# IDC_EXT_Connectors.net
KiCad netlist of a schematic drawn in Altium Designer
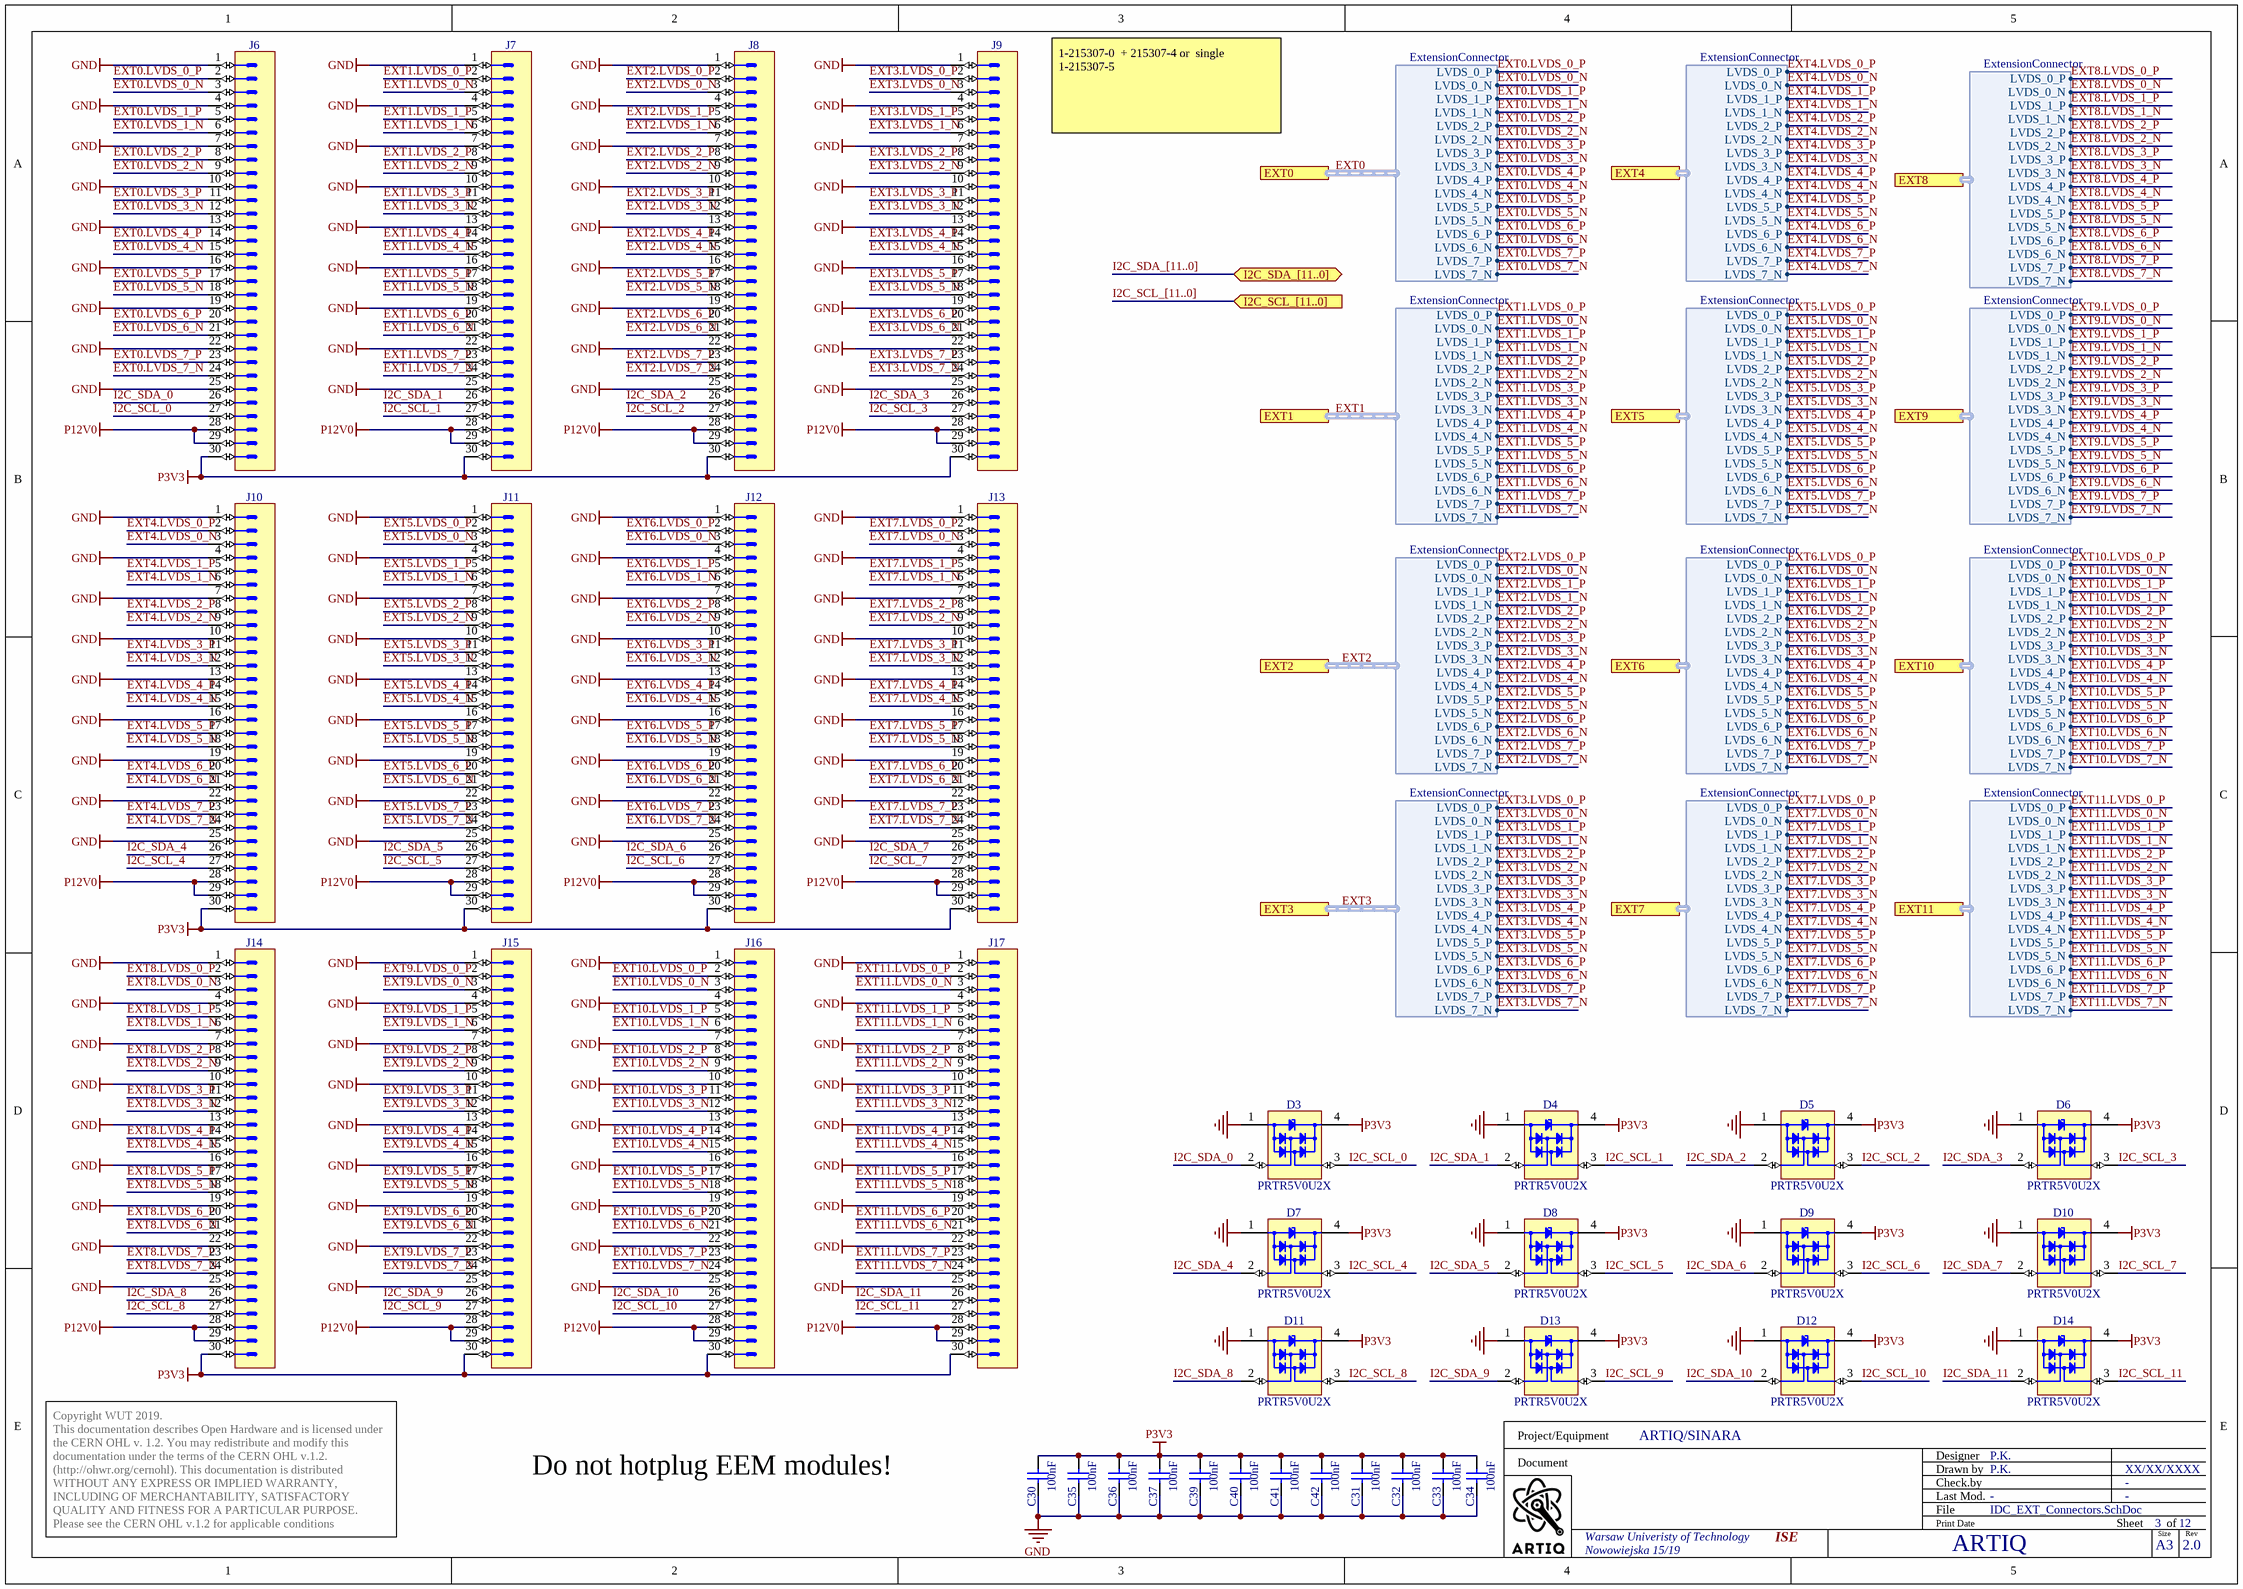
[diagram p0: IDC_EXT_Connectors.SchDoc]

(export (version "E")
  (design (tool "Eeschema 10.0.6"))
  (components
    (comp (ref "C30")
      (value "100nF")
      (footprint "CAPC0603X33N")
      (description "Non-polarised capacitor")
      (fields
        (field (name "PART NUMBER") "CC0201_100NF_6.3V_10%_X5R")
        (field (name "VOLTAGE") "6.3V")
        (field (name "AUTHOR") "CERN DEM JLC")
      )
      (libsource (lib "Capacitors") (part "Capacitor - non polarized"))
    )
    (comp (ref "C31")
      (value "100nF")
      (footprint "CAPC0603X33N")
      (description "Non-polarised capacitor")
      (fields
        (field (name "PART NUMBER") "CC0201_100NF_6.3V_10%_X5R")
        (field (name "VOLTAGE") "6.3V")
        (field (name "AUTHOR") "CERN DEM JLC")
      )
      (libsource (lib "Capacitors") (part "Capacitor - non polarized"))
    )
    (comp (ref "C32")
      (value "100nF")
      (footprint "CAPC0603X33N")
      (description "Non-polarised capacitor")
      (fields
        (field (name "PART NUMBER") "CC0201_100NF_6.3V_10%_X5R")
        (field (name "VOLTAGE") "6.3V")
        (field (name "AUTHOR") "CERN DEM JLC")
      )
      (libsource (lib "Capacitors") (part "Capacitor - non polarized"))
    )
    (comp (ref "C33")
      (value "100nF")
      (footprint "CAPC0603X33N")
      (description "Non-polarised capacitor")
      (fields
        (field (name "PART NUMBER") "CC0201_100NF_6.3V_10%_X5R")
        (field (name "VOLTAGE") "6.3V")
        (field (name "AUTHOR") "CERN DEM JLC")
      )
      (libsource (lib "Capacitors") (part "Capacitor - non polarized"))
    )
    (comp (ref "C34")
      (value "100nF")
      (footprint "CAPC0603X33N")
      (description "Non-polarised capacitor")
      (fields
        (field (name "PART NUMBER") "CC0201_100NF_6.3V_10%_X5R")
        (field (name "VOLTAGE") "6.3V")
        (field (name "AUTHOR") "CERN DEM JLC")
      )
      (libsource (lib "Capacitors") (part "Capacitor - non polarized"))
    )
    (comp (ref "C35")
      (value "100nF")
      (footprint "CAPC0603X33N")
      (description "Non-polarised capacitor")
      (fields
        (field (name "PART NUMBER") "CC0201_100NF_6.3V_10%_X5R")
        (field (name "VOLTAGE") "6.3V")
        (field (name "AUTHOR") "CERN DEM JLC")
      )
      (libsource (lib "Capacitors") (part "Capacitor - non polarized"))
    )
    (comp (ref "C36")
      (value "100nF")
      (footprint "CAPC0603X33N")
      (description "Non-polarised capacitor")
      (fields
        (field (name "PART NUMBER") "CC0201_100NF_6.3V_10%_X5R")
        (field (name "VOLTAGE") "6.3V")
        (field (name "AUTHOR") "CERN DEM JLC")
      )
      (libsource (lib "Capacitors") (part "Capacitor - non polarized"))
    )
    (comp (ref "C37")
      (value "100nF")
      (footprint "CAPC0603X33N")
      (description "Non-polarised capacitor")
      (fields
        (field (name "PART NUMBER") "CC0201_100NF_6.3V_10%_X5R")
        (field (name "VOLTAGE") "6.3V")
        (field (name "AUTHOR") "CERN DEM JLC")
      )
      (libsource (lib "Capacitors") (part "Capacitor - non polarized"))
    )
    (comp (ref "C39")
      (value "100nF")
      (footprint "CAPC0603X33N")
      (description "Non-polarised capacitor")
      (fields
        (field (name "PART NUMBER") "CC0201_100NF_6.3V_10%_X5R")
        (field (name "VOLTAGE") "6.3V")
        (field (name "AUTHOR") "CERN DEM JLC")
      )
      (libsource (lib "Capacitors") (part "Capacitor - non polarized"))
    )
    (comp (ref "C40")
      (value "100nF")
      (footprint "CAPC0603X33N")
      (description "Non-polarised capacitor")
      (fields
        (field (name "PART NUMBER") "CC0201_100NF_6.3V_10%_X5R")
        (field (name "VOLTAGE") "6.3V")
        (field (name "AUTHOR") "CERN DEM JLC")
      )
      (libsource (lib "Capacitors") (part "Capacitor - non polarized"))
    )
    (comp (ref "C41")
      (value "100nF")
      (footprint "CAPC0603X33N")
      (description "Non-polarised capacitor")
      (fields
        (field (name "PART NUMBER") "CC0201_100NF_6.3V_10%_X5R")
        (field (name "VOLTAGE") "6.3V")
        (field (name "AUTHOR") "CERN DEM JLC")
      )
      (libsource (lib "Capacitors") (part "Capacitor - non polarized"))
    )
    (comp (ref "C42")
      (value "100nF")
      (footprint "CAPC0603X33N")
      (description "Non-polarised capacitor")
      (fields
        (field (name "PART NUMBER") "CC0201_100NF_6.3V_10%_X5R")
        (field (name "VOLTAGE") "6.3V")
        (field (name "AUTHOR") "CERN DEM JLC")
      )
      (libsource (lib "Capacitors") (part "Capacitor - non polarized"))
    )
    (comp (ref "D3")
      (value "PRTR5V0U2X")
      (footprint "SOT190P230X110-4N")
      (description "Ultra Low Capacitance Double Rail-to-Rail ESD Protection Diode")
      (fields
        (field (name "VOLTAGE") "5.5V")
        (field (name "MANUFACTURER") "NXP SEMICONDUCTORS")
        (field (name "AUTHOR") "CERN DEM JLC")
      )
      (libsource (lib "ICs And Semiconductors") (part "PRTR5V0U2X"))
    )
    (comp (ref "D4")
      (value "PRTR5V0U2X")
      (footprint "SOT190P230X110-4N")
      (description "Ultra Low Capacitance Double Rail-to-Rail ESD Protection Diode")
      (fields
        (field (name "VOLTAGE") "5.5V")
        (field (name "MANUFACTURER") "NXP SEMICONDUCTORS")
        (field (name "AUTHOR") "CERN DEM JLC")
      )
      (libsource (lib "ICs And Semiconductors") (part "PRTR5V0U2X"))
    )
    (comp (ref "D5")
      (value "PRTR5V0U2X")
      (footprint "SOT190P230X110-4N")
      (description "Ultra Low Capacitance Double Rail-to-Rail ESD Protection Diode")
      (fields
        (field (name "VOLTAGE") "5.5V")
        (field (name "MANUFACTURER") "NXP SEMICONDUCTORS")
        (field (name "AUTHOR") "CERN DEM JLC")
      )
      (libsource (lib "ICs And Semiconductors") (part "PRTR5V0U2X"))
    )
    (comp (ref "D6")
      (value "PRTR5V0U2X")
      (footprint "SOT190P230X110-4N")
      (description "Ultra Low Capacitance Double Rail-to-Rail ESD Protection Diode")
      (fields
        (field (name "VOLTAGE") "5.5V")
        (field (name "MANUFACTURER") "NXP SEMICONDUCTORS")
        (field (name "AUTHOR") "CERN DEM JLC")
      )
      (libsource (lib "ICs And Semiconductors") (part "PRTR5V0U2X"))
    )
    (comp (ref "D7")
      (value "PRTR5V0U2X")
      (footprint "SOT190P230X110-4N")
      (description "Ultra Low Capacitance Double Rail-to-Rail ESD Protection Diode")
      (fields
        (field (name "VOLTAGE") "5.5V")
        (field (name "MANUFACTURER") "NXP SEMICONDUCTORS")
        (field (name "AUTHOR") "CERN DEM JLC")
      )
      (libsource (lib "ICs And Semiconductors") (part "PRTR5V0U2X"))
    )
    (comp (ref "D8")
      (value "PRTR5V0U2X")
      (footprint "SOT190P230X110-4N")
      (description "Ultra Low Capacitance Double Rail-to-Rail ESD Protection Diode")
      (fields
        (field (name "VOLTAGE") "5.5V")
        (field (name "MANUFACTURER") "NXP SEMICONDUCTORS")
        (field (name "AUTHOR") "CERN DEM JLC")
      )
      (libsource (lib "ICs And Semiconductors") (part "PRTR5V0U2X"))
    )
    (comp (ref "D9")
      (value "PRTR5V0U2X")
      (footprint "SOT190P230X110-4N")
      (description "Ultra Low Capacitance Double Rail-to-Rail ESD Protection Diode")
      (fields
        (field (name "VOLTAGE") "5.5V")
        (field (name "MANUFACTURER") "NXP SEMICONDUCTORS")
        (field (name "AUTHOR") "CERN DEM JLC")
      )
      (libsource (lib "ICs And Semiconductors") (part "PRTR5V0U2X"))
    )
    (comp (ref "D10")
      (value "PRTR5V0U2X")
      (footprint "SOT190P230X110-4N")
      (description "Ultra Low Capacitance Double Rail-to-Rail ESD Protection Diode")
      (fields
        (field (name "VOLTAGE") "5.5V")
        (field (name "MANUFACTURER") "NXP SEMICONDUCTORS")
        (field (name "AUTHOR") "CERN DEM JLC")
      )
      (libsource (lib "ICs And Semiconductors") (part "PRTR5V0U2X"))
    )
    (comp (ref "D11")
      (value "PRTR5V0U2X")
      (footprint "SOT190P230X110-4N")
      (description "Ultra Low Capacitance Double Rail-to-Rail ESD Protection Diode")
      (fields
        (field (name "VOLTAGE") "5.5V")
        (field (name "MANUFACTURER") "NXP SEMICONDUCTORS")
        (field (name "AUTHOR") "CERN DEM JLC")
      )
      (libsource (lib "ICs And Semiconductors") (part "PRTR5V0U2X"))
    )
    (comp (ref "D12")
      (value "PRTR5V0U2X")
      (footprint "SOT190P230X110-4N")
      (description "Ultra Low Capacitance Double Rail-to-Rail ESD Protection Diode")
      (fields
        (field (name "VOLTAGE") "5.5V")
        (field (name "MANUFACTURER") "NXP SEMICONDUCTORS")
        (field (name "AUTHOR") "CERN DEM JLC")
      )
      (libsource (lib "ICs And Semiconductors") (part "PRTR5V0U2X"))
    )
    (comp (ref "D13")
      (value "PRTR5V0U2X")
      (footprint "SOT190P230X110-4N")
      (description "Ultra Low Capacitance Double Rail-to-Rail ESD Protection Diode")
      (fields
        (field (name "VOLTAGE") "5.5V")
        (field (name "MANUFACTURER") "NXP SEMICONDUCTORS")
        (field (name "AUTHOR") "CERN DEM JLC")
      )
      (libsource (lib "ICs And Semiconductors") (part "PRTR5V0U2X"))
    )
    (comp (ref "D14")
      (value "PRTR5V0U2X")
      (footprint "SOT190P230X110-4N")
      (description "Ultra Low Capacitance Double Rail-to-Rail ESD Protection Diode")
      (fields
        (field (name "VOLTAGE") "5.5V")
        (field (name "MANUFACTURER") "NXP SEMICONDUCTORS")
        (field (name "AUTHOR") "CERN DEM JLC")
      )
      (libsource (lib "ICs And Semiconductors") (part "PRTR5V0U2X"))
    )
    (comp (ref "J6")
      (value "AMPMODU")
      (footprint "TYCO_1-215307-5")
      (description "Connector 2.54mm, 30 pin female, vertical, 7mm, AMPMODU HV-100/HV-190")
      (fields
        (field (name "PART NUMBER") "TYCO_1-215307-5")
        (field (name "MANUFACTURER") "TYCO ELECTRONICS")
        (field (name "AUTHOR") "GK")
      )
      (libsource (lib "LIBRARY_SCH") (part "CON_2x15_2.54_female_V_mirror"))
    )
    (comp (ref "J7")
      (value "AMPMODU")
      (footprint "TYCO_1-215307-5")
      (description "Connector 2.54mm, 30 pin female, vertical, 7mm, AMPMODU HV-100/HV-190")
      (fields
        (field (name "PART NUMBER") "TYCO_1-215307-5")
        (field (name "MANUFACTURER") "TYCO ELECTRONICS")
        (field (name "AUTHOR") "GK")
      )
      (libsource (lib "LIBRARY_SCH") (part "CON_2x15_2.54_female_V_mirror"))
    )
    (comp (ref "J8")
      (value "AMPMODU")
      (footprint "TYCO_1-215307-5")
      (description "Connector 2.54mm, 30 pin female, vertical, 7mm, AMPMODU HV-100/HV-190")
      (fields
        (field (name "PART NUMBER") "TYCO_1-215307-5")
        (field (name "MANUFACTURER") "TYCO ELECTRONICS")
        (field (name "AUTHOR") "GK")
      )
      (libsource (lib "LIBRARY_SCH") (part "CON_2x15_2.54_female_V_mirror"))
    )
    (comp (ref "J9")
      (value "AMPMODU")
      (footprint "TYCO_1-215307-5")
      (description "Connector 2.54mm, 30 pin female, vertical, 7mm, AMPMODU HV-100/HV-190")
      (fields
        (field (name "PART NUMBER") "TYCO_1-215307-5")
        (field (name "MANUFACTURER") "TYCO ELECTRONICS")
        (field (name "AUTHOR") "GK")
      )
      (libsource (lib "LIBRARY_SCH") (part "CON_2x15_2.54_female_V_mirror"))
    )
    (comp (ref "J10")
      (value "AMPMODU")
      (footprint "TYCO_1-215307-5")
      (description "Connector 2.54mm, 30 pin female, vertical, 7mm, AMPMODU HV-100/HV-190")
      (fields
        (field (name "PART NUMBER") "TYCO_1-215307-5")
        (field (name "MANUFACTURER") "TYCO ELECTRONICS")
        (field (name "AUTHOR") "GK")
      )
      (libsource (lib "LIBRARY_SCH") (part "CON_2x15_2.54_female_V_mirror"))
    )
    (comp (ref "J11")
      (value "AMPMODU")
      (footprint "TYCO_1-215307-5")
      (description "Connector 2.54mm, 30 pin female, vertical, 7mm, AMPMODU HV-100/HV-190")
      (fields
        (field (name "PART NUMBER") "TYCO_1-215307-5")
        (field (name "MANUFACTURER") "TYCO ELECTRONICS")
        (field (name "AUTHOR") "GK")
      )
      (libsource (lib "LIBRARY_SCH") (part "CON_2x15_2.54_female_V_mirror"))
    )
    (comp (ref "J12")
      (value "AMPMODU")
      (footprint "TYCO_1-215307-5")
      (description "Connector 2.54mm, 30 pin female, vertical, 7mm, AMPMODU HV-100/HV-190")
      (fields
        (field (name "PART NUMBER") "TYCO_1-215307-5")
        (field (name "MANUFACTURER") "TYCO ELECTRONICS")
        (field (name "AUTHOR") "GK")
      )
      (libsource (lib "LIBRARY_SCH") (part "CON_2x15_2.54_female_V_mirror"))
    )
    (comp (ref "J13")
      (value "AMPMODU")
      (footprint "TYCO_1-215307-5")
      (description "Connector 2.54mm, 30 pin female, vertical, 7mm, AMPMODU HV-100/HV-190")
      (fields
        (field (name "PART NUMBER") "TYCO_1-215307-5")
        (field (name "MANUFACTURER") "TYCO ELECTRONICS")
        (field (name "AUTHOR") "GK")
      )
      (libsource (lib "LIBRARY_SCH") (part "CON_2x15_2.54_female_V_mirror"))
    )
    (comp (ref "J14")
      (value "AMPMODU")
      (footprint "TYCO_1-215307-5")
      (description "Connector 2.54mm, 30 pin female, vertical, 7mm, AMPMODU HV-100/HV-190")
      (fields
        (field (name "PART NUMBER") "TYCO_1-215307-5")
        (field (name "MANUFACTURER") "TYCO ELECTRONICS")
        (field (name "AUTHOR") "GK")
      )
      (libsource (lib "LIBRARY_SCH") (part "CON_2x15_2.54_female_V_mirror"))
    )
    (comp (ref "J15")
      (value "AMPMODU")
      (footprint "TYCO_1-215307-5")
      (description "Connector 2.54mm, 30 pin female, vertical, 7mm, AMPMODU HV-100/HV-190")
      (fields
        (field (name "PART NUMBER") "TYCO_1-215307-5")
        (field (name "MANUFACTURER") "TYCO ELECTRONICS")
        (field (name "AUTHOR") "GK")
      )
      (libsource (lib "LIBRARY_SCH") (part "CON_2x15_2.54_female_V_mirror"))
    )
    (comp (ref "J16")
      (value "AMPMODU")
      (footprint "TYCO_1-215307-5")
      (description "Connector 2.54mm, 30 pin female, vertical, 7mm, AMPMODU HV-100/HV-190")
      (fields
        (field (name "PART NUMBER") "TYCO_1-215307-5")
        (field (name "MANUFACTURER") "TYCO ELECTRONICS")
        (field (name "AUTHOR") "GK")
      )
      (libsource (lib "LIBRARY_SCH") (part "CON_2x15_2.54_female_V_mirror"))
    )
    (comp (ref "J17")
      (value "AMPMODU")
      (footprint "TYCO_1-215307-5")
      (description "Connector 2.54mm, 30 pin female, vertical, 7mm, AMPMODU HV-100/HV-190")
      (fields
        (field (name "PART NUMBER") "TYCO_1-215307-5")
        (field (name "MANUFACTURER") "TYCO ELECTRONICS")
        (field (name "AUTHOR") "GK")
      )
      (libsource (lib "LIBRARY_SCH") (part "CON_2x15_2.54_female_V_mirror"))
    )
  )
  (nets
    (net (code "6") (name "/EXT0.LVDS_0_N") (class "Default")
      (node (ref "J6") (pin "3") (pinfunction "3_3") (pintype "bidirectional"))
    )
    (net (code "7") (name "/EXT0.LVDS_0_P") (class "Default")
      (node (ref "J6") (pin "2") (pinfunction "2_2") (pintype "bidirectional"))
    )
    (net (code "8") (name "/EXT0.LVDS_1_N") (class "Default")
      (node (ref "J6") (pin "6") (pinfunction "6_6") (pintype "bidirectional"))
    )
    (net (code "9") (name "/EXT0.LVDS_1_P") (class "Default")
      (node (ref "J6") (pin "5") (pinfunction "5_5") (pintype "bidirectional"))
    )
    (net (code "10") (name "/EXT0.LVDS_2_N") (class "Default")
      (node (ref "J6") (pin "9") (pinfunction "9_9") (pintype "bidirectional"))
    )
    (net (code "11") (name "/EXT0.LVDS_2_P") (class "Default")
      (node (ref "J6") (pin "8") (pinfunction "8_8") (pintype "bidirectional"))
    )
    (net (code "12") (name "/EXT0.LVDS_3_N") (class "Default")
      (node (ref "J6") (pin "12") (pinfunction "12_12") (pintype "bidirectional"))
    )
    (net (code "13") (name "/EXT0.LVDS_3_P") (class "Default")
      (node (ref "J6") (pin "11") (pinfunction "11_11") (pintype "bidirectional"))
    )
    (net (code "14") (name "/EXT0.LVDS_4_N") (class "Default")
      (node (ref "J6") (pin "15") (pinfunction "15_15") (pintype "bidirectional"))
    )
    (net (code "15") (name "/EXT0.LVDS_4_P") (class "Default")
      (node (ref "J6") (pin "14") (pinfunction "14_14") (pintype "bidirectional"))
    )
    (net (code "16") (name "/EXT0.LVDS_5_N") (class "Default")
      (node (ref "J6") (pin "18") (pinfunction "18_18") (pintype "bidirectional"))
    )
    (net (code "17") (name "/EXT0.LVDS_5_P") (class "Default")
      (node (ref "J6") (pin "17") (pinfunction "17_17") (pintype "bidirectional"))
    )
    (net (code "18") (name "/EXT0.LVDS_6_N") (class "Default")
      (node (ref "J6") (pin "21") (pinfunction "21_21") (pintype "bidirectional"))
    )
    (net (code "19") (name "/EXT0.LVDS_6_P") (class "Default")
      (node (ref "J6") (pin "20") (pinfunction "20_20") (pintype "bidirectional"))
    )
    (net (code "20") (name "/EXT0.LVDS_7_N") (class "Default")
      (node (ref "J6") (pin "24") (pinfunction "24_24") (pintype "bidirectional"))
    )
    (net (code "21") (name "/EXT0.LVDS_7_P") (class "Default")
      (node (ref "J6") (pin "23") (pinfunction "23_23") (pintype "bidirectional"))
    )
    (net (code "23") (name "/EXT1.LVDS_0_N") (class "Default")
      (node (ref "J7") (pin "3") (pinfunction "3_3") (pintype "bidirectional"))
    )
    (net (code "24") (name "/EXT1.LVDS_0_P") (class "Default")
      (node (ref "J7") (pin "2") (pinfunction "2_2") (pintype "bidirectional"))
    )
    (net (code "25") (name "/EXT1.LVDS_1_N") (class "Default")
      (node (ref "J7") (pin "6") (pinfunction "6_6") (pintype "bidirectional"))
    )
    (net (code "26") (name "/EXT1.LVDS_1_P") (class "Default")
      (node (ref "J7") (pin "5") (pinfunction "5_5") (pintype "bidirectional"))
    )
    (net (code "27") (name "/EXT1.LVDS_2_N") (class "Default")
      (node (ref "J7") (pin "9") (pinfunction "9_9") (pintype "bidirectional"))
    )
    (net (code "28") (name "/EXT1.LVDS_2_P") (class "Default")
      (node (ref "J7") (pin "8") (pinfunction "8_8") (pintype "bidirectional"))
    )
    (net (code "29") (name "/EXT1.LVDS_3_N") (class "Default")
      (node (ref "J7") (pin "12") (pinfunction "12_12") (pintype "bidirectional"))
    )
    (net (code "30") (name "/EXT1.LVDS_3_P") (class "Default")
      (node (ref "J7") (pin "11") (pinfunction "11_11") (pintype "bidirectional"))
    )
    (net (code "31") (name "/EXT1.LVDS_4_N") (class "Default")
      (node (ref "J7") (pin "15") (pinfunction "15_15") (pintype "bidirectional"))
    )
    (net (code "32") (name "/EXT1.LVDS_4_P") (class "Default")
      (node (ref "J7") (pin "14") (pinfunction "14_14") (pintype "bidirectional"))
    )
    (net (code "33") (name "/EXT1.LVDS_5_N") (class "Default")
      (node (ref "J7") (pin "18") (pinfunction "18_18") (pintype "bidirectional"))
    )
    (net (code "34") (name "/EXT1.LVDS_5_P") (class "Default")
      (node (ref "J7") (pin "17") (pinfunction "17_17") (pintype "bidirectional"))
    )
    (net (code "35") (name "/EXT1.LVDS_6_N") (class "Default")
      (node (ref "J7") (pin "21") (pinfunction "21_21") (pintype "bidirectional"))
    )
    (net (code "36") (name "/EXT1.LVDS_6_P") (class "Default")
      (node (ref "J7") (pin "20") (pinfunction "20_20") (pintype "bidirectional"))
    )
    (net (code "37") (name "/EXT1.LVDS_7_N") (class "Default")
      (node (ref "J7") (pin "24") (pinfunction "24_24") (pintype "bidirectional"))
    )
    (net (code "38") (name "/EXT1.LVDS_7_P") (class "Default")
      (node (ref "J7") (pin "23") (pinfunction "23_23") (pintype "bidirectional"))
    )
    (net (code "40") (name "/EXT2.LVDS_0_N") (class "Default")
      (node (ref "J8") (pin "3") (pinfunction "3_3") (pintype "bidirectional"))
    )
    (net (code "41") (name "/EXT2.LVDS_0_P") (class "Default")
      (node (ref "J8") (pin "2") (pinfunction "2_2") (pintype "bidirectional"))
    )
    (net (code "42") (name "/EXT2.LVDS_1_N") (class "Default")
      (node (ref "J8") (pin "6") (pinfunction "6_6") (pintype "bidirectional"))
    )
    (net (code "43") (name "/EXT2.LVDS_1_P") (class "Default")
      (node (ref "J8") (pin "5") (pinfunction "5_5") (pintype "bidirectional"))
    )
    (net (code "44") (name "/EXT2.LVDS_2_N") (class "Default")
      (node (ref "J8") (pin "9") (pinfunction "9_9") (pintype "bidirectional"))
    )
    (net (code "45") (name "/EXT2.LVDS_2_P") (class "Default")
      (node (ref "J8") (pin "8") (pinfunction "8_8") (pintype "bidirectional"))
    )
    (net (code "46") (name "/EXT2.LVDS_3_N") (class "Default")
      (node (ref "J8") (pin "12") (pinfunction "12_12") (pintype "bidirectional"))
    )
    (net (code "47") (name "/EXT2.LVDS_3_P") (class "Default")
      (node (ref "J8") (pin "11") (pinfunction "11_11") (pintype "bidirectional"))
    )
    (net (code "48") (name "/EXT2.LVDS_4_N") (class "Default")
      (node (ref "J8") (pin "15") (pinfunction "15_15") (pintype "bidirectional"))
    )
    (net (code "49") (name "/EXT2.LVDS_4_P") (class "Default")
      (node (ref "J8") (pin "14") (pinfunction "14_14") (pintype "bidirectional"))
    )
    (net (code "50") (name "/EXT2.LVDS_5_N") (class "Default")
      (node (ref "J8") (pin "18") (pinfunction "18_18") (pintype "bidirectional"))
    )
    (net (code "51") (name "/EXT2.LVDS_5_P") (class "Default")
      (node (ref "J8") (pin "17") (pinfunction "17_17") (pintype "bidirectional"))
    )
    (net (code "52") (name "/EXT2.LVDS_6_N") (class "Default")
      (node (ref "J8") (pin "21") (pinfunction "21_21") (pintype "bidirectional"))
    )
    (net (code "53") (name "/EXT2.LVDS_6_P") (class "Default")
      (node (ref "J8") (pin "20") (pinfunction "20_20") (pintype "bidirectional"))
    )
    (net (code "54") (name "/EXT2.LVDS_7_N") (class "Default")
      (node (ref "J8") (pin "24") (pinfunction "24_24") (pintype "bidirectional"))
    )
    (net (code "55") (name "/EXT2.LVDS_7_P") (class "Default")
      (node (ref "J8") (pin "23") (pinfunction "23_23") (pintype "bidirectional"))
    )
    (net (code "57") (name "/EXT3.LVDS_0_N") (class "Default")
      (node (ref "J9") (pin "3") (pinfunction "3_3") (pintype "bidirectional"))
    )
    (net (code "58") (name "/EXT3.LVDS_0_P") (class "Default")
      (node (ref "J9") (pin "2") (pinfunction "2_2") (pintype "bidirectional"))
    )
    (net (code "59") (name "/EXT3.LVDS_1_N") (class "Default")
      (node (ref "J9") (pin "6") (pinfunction "6_6") (pintype "bidirectional"))
    )
    (net (code "60") (name "/EXT3.LVDS_1_P") (class "Default")
      (node (ref "J9") (pin "5") (pinfunction "5_5") (pintype "bidirectional"))
    )
    (net (code "61") (name "/EXT3.LVDS_2_N") (class "Default")
      (node (ref "J9") (pin "9") (pinfunction "9_9") (pintype "bidirectional"))
    )
    (net (code "62") (name "/EXT3.LVDS_2_P") (class "Default")
      (node (ref "J9") (pin "8") (pinfunction "8_8") (pintype "bidirectional"))
    )
    (net (code "63") (name "/EXT3.LVDS_3_N") (class "Default")
      (node (ref "J9") (pin "12") (pinfunction "12_12") (pintype "bidirectional"))
    )
    (net (code "64") (name "/EXT3.LVDS_3_P") (class "Default")
      (node (ref "J9") (pin "11") (pinfunction "11_11") (pintype "bidirectional"))
    )
    (net (code "65") (name "/EXT3.LVDS_4_N") (class "Default")
      (node (ref "J9") (pin "15") (pinfunction "15_15") (pintype "bidirectional"))
    )
    (net (code "66") (name "/EXT3.LVDS_4_P") (class "Default")
      (node (ref "J9") (pin "14") (pinfunction "14_14") (pintype "bidirectional"))
    )
    (net (code "67") (name "/EXT3.LVDS_5_N") (class "Default")
      (node (ref "J9") (pin "18") (pinfunction "18_18") (pintype "bidirectional"))
    )
    (net (code "68") (name "/EXT3.LVDS_5_P") (class "Default")
      (node (ref "J9") (pin "17") (pinfunction "17_17") (pintype "bidirectional"))
    )
    (net (code "69") (name "/EXT3.LVDS_6_N") (class "Default")
      (node (ref "J9") (pin "21") (pinfunction "21_21") (pintype "bidirectional"))
    )
    (net (code "70") (name "/EXT3.LVDS_6_P") (class "Default")
      (node (ref "J9") (pin "20") (pinfunction "20_20") (pintype "bidirectional"))
    )
    (net (code "71") (name "/EXT3.LVDS_7_N") (class "Default")
      (node (ref "J9") (pin "24") (pinfunction "24_24") (pintype "bidirectional"))
    )
    (net (code "72") (name "/EXT3.LVDS_7_P") (class "Default")
      (node (ref "J9") (pin "23") (pinfunction "23_23") (pintype "bidirectional"))
    )
    (net (code "74") (name "/EXT4.LVDS_0_N") (class "Default")
      (node (ref "J10") (pin "3") (pinfunction "3_3") (pintype "bidirectional"))
    )
    (net (code "75") (name "/EXT4.LVDS_0_P") (class "Default")
      (node (ref "J10") (pin "2") (pinfunction "2_2") (pintype "bidirectional"))
    )
    (net (code "76") (name "/EXT4.LVDS_1_N") (class "Default")
      (node (ref "J10") (pin "6") (pinfunction "6_6") (pintype "bidirectional"))
    )
    (net (code "77") (name "/EXT4.LVDS_1_P") (class "Default")
      (node (ref "J10") (pin "5") (pinfunction "5_5") (pintype "bidirectional"))
    )
    (net (code "78") (name "/EXT4.LVDS_2_N") (class "Default")
      (node (ref "J10") (pin "9") (pinfunction "9_9") (pintype "bidirectional"))
    )
    (net (code "79") (name "/EXT4.LVDS_2_P") (class "Default")
      (node (ref "J10") (pin "8") (pinfunction "8_8") (pintype "bidirectional"))
    )
    (net (code "80") (name "/EXT4.LVDS_3_N") (class "Default")
      (node (ref "J10") (pin "12") (pinfunction "12_12") (pintype "bidirectional"))
    )
    (net (code "81") (name "/EXT4.LVDS_3_P") (class "Default")
      (node (ref "J10") (pin "11") (pinfunction "11_11") (pintype "bidirectional"))
    )
    (net (code "82") (name "/EXT4.LVDS_4_N") (class "Default")
      (node (ref "J10") (pin "15") (pinfunction "15_15") (pintype "bidirectional"))
    )
    (net (code "83") (name "/EXT4.LVDS_4_P") (class "Default")
      (node (ref "J10") (pin "14") (pinfunction "14_14") (pintype "bidirectional"))
    )
    (net (code "84") (name "/EXT4.LVDS_5_N") (class "Default")
      (node (ref "J10") (pin "18") (pinfunction "18_18") (pintype "bidirectional"))
    )
    (net (code "85") (name "/EXT4.LVDS_5_P") (class "Default")
      (node (ref "J10") (pin "17") (pinfunction "17_17") (pintype "bidirectional"))
    )
    (net (code "86") (name "/EXT4.LVDS_6_N") (class "Default")
      (node (ref "J10") (pin "21") (pinfunction "21_21") (pintype "bidirectional"))
    )
    (net (code "87") (name "/EXT4.LVDS_6_P") (class "Default")
      (node (ref "J10") (pin "20") (pinfunction "20_20") (pintype "bidirectional"))
    )
    (net (code "88") (name "/EXT4.LVDS_7_N") (class "Default")
      (node (ref "J10") (pin "24") (pinfunction "24_24") (pintype "bidirectional"))
    )
    (net (code "89") (name "/EXT4.LVDS_7_P") (class "Default")
      (node (ref "J10") (pin "23") (pinfunction "23_23") (pintype "bidirectional"))
    )
    (net (code "90") (name "/EXT5.LVDS_0_N") (class "Default")
      (node (ref "J11") (pin "3") (pinfunction "3_3") (pintype "bidirectional"))
    )
    (net (code "91") (name "/EXT5.LVDS_0_P") (class "Default")
      (node (ref "J11") (pin "2") (pinfunction "2_2") (pintype "bidirectional"))
    )
    (net (code "92") (name "/EXT5.LVDS_1_N") (class "Default")
      (node (ref "J11") (pin "6") (pinfunction "6_6") (pintype "bidirectional"))
    )
    (net (code "93") (name "/EXT5.LVDS_1_P") (class "Default")
      (node (ref "J11") (pin "5") (pinfunction "5_5") (pintype "bidirectional"))
    )
    (net (code "94") (name "/EXT5.LVDS_2_N") (class "Default")
      (node (ref "J11") (pin "9") (pinfunction "9_9") (pintype "bidirectional"))
    )
    (net (code "95") (name "/EXT5.LVDS_2_P") (class "Default")
      (node (ref "J11") (pin "8") (pinfunction "8_8") (pintype "bidirectional"))
    )
    (net (code "96") (name "/EXT5.LVDS_3_N") (class "Default")
      (node (ref "J11") (pin "12") (pinfunction "12_12") (pintype "bidirectional"))
    )
    (net (code "97") (name "/EXT5.LVDS_3_P") (class "Default")
      (node (ref "J11") (pin "11") (pinfunction "11_11") (pintype "bidirectional"))
    )
    (net (code "98") (name "/EXT5.LVDS_4_N") (class "Default")
      (node (ref "J11") (pin "15") (pinfunction "15_15") (pintype "bidirectional"))
    )
    (net (code "99") (name "/EXT5.LVDS_4_P") (class "Default")
      (node (ref "J11") (pin "14") (pinfunction "14_14") (pintype "bidirectional"))
    )
    (net (code "100") (name "/EXT5.LVDS_5_N") (class "Default")
      (node (ref "J11") (pin "18") (pinfunction "18_18") (pintype "bidirectional"))
    )
    (net (code "101") (name "/EXT5.LVDS_5_P") (class "Default")
      (node (ref "J11") (pin "17") (pinfunction "17_17") (pintype "bidirectional"))
    )
    (net (code "102") (name "/EXT5.LVDS_6_N") (class "Default")
      (node (ref "J11") (pin "21") (pinfunction "21_21") (pintype "bidirectional"))
    )
    (net (code "103") (name "/EXT5.LVDS_6_P") (class "Default")
      (node (ref "J11") (pin "20") (pinfunction "20_20") (pintype "bidirectional"))
    )
    (net (code "104") (name "/EXT5.LVDS_7_N") (class "Default")
      (node (ref "J11") (pin "24") (pinfunction "24_24") (pintype "bidirectional"))
    )
    (net (code "105") (name "/EXT5.LVDS_7_P") (class "Default")
      (node (ref "J11") (pin "23") (pinfunction "23_23") (pintype "bidirectional"))
    )
    (net (code "106") (name "/EXT6.LVDS_0_N") (class "Default")
      (node (ref "J12") (pin "3") (pinfunction "3_3") (pintype "bidirectional"))
    )
    (net (code "107") (name "/EXT6.LVDS_0_P") (class "Default")
      (node (ref "J12") (pin "2") (pinfunction "2_2") (pintype "bidirectional"))
    )
    (net (code "108") (name "/EXT6.LVDS_1_N") (class "Default")
      (node (ref "J12") (pin "6") (pinfunction "6_6") (pintype "bidirectional"))
    )
    (net (code "109") (name "/EXT6.LVDS_1_P") (class "Default")
      (node (ref "J12") (pin "5") (pinfunction "5_5") (pintype "bidirectional"))
    )
    (net (code "110") (name "/EXT6.LVDS_2_N") (class "Default")
      (node (ref "J12") (pin "9") (pinfunction "9_9") (pintype "bidirectional"))
    )
    (net (code "111") (name "/EXT6.LVDS_2_P") (class "Default")
      (node (ref "J12") (pin "8") (pinfunction "8_8") (pintype "bidirectional"))
    )
    (net (code "112") (name "/EXT6.LVDS_3_N") (class "Default")
      (node (ref "J12") (pin "12") (pinfunction "12_12") (pintype "bidirectional"))
    )
    (net (code "113") (name "/EXT6.LVDS_3_P") (class "Default")
      (node (ref "J12") (pin "11") (pinfunction "11_11") (pintype "bidirectional"))
    )
    (net (code "114") (name "/EXT6.LVDS_4_N") (class "Default")
      (node (ref "J12") (pin "15") (pinfunction "15_15") (pintype "bidirectional"))
    )
    (net (code "115") (name "/EXT6.LVDS_4_P") (class "Default")
      (node (ref "J12") (pin "14") (pinfunction "14_14") (pintype "bidirectional"))
    )
    (net (code "116") (name "/EXT6.LVDS_5_N") (class "Default")
      (node (ref "J12") (pin "18") (pinfunction "18_18") (pintype "bidirectional"))
    )
    (net (code "117") (name "/EXT6.LVDS_5_P") (class "Default")
      (node (ref "J12") (pin "17") (pinfunction "17_17") (pintype "bidirectional"))
    )
    (net (code "118") (name "/EXT6.LVDS_6_N") (class "Default")
      (node (ref "J12") (pin "21") (pinfunction "21_21") (pintype "bidirectional"))
    )
    (net (code "119") (name "/EXT6.LVDS_6_P") (class "Default")
      (node (ref "J12") (pin "20") (pinfunction "20_20") (pintype "bidirectional"))
    )
    (net (code "120") (name "/EXT6.LVDS_7_N") (class "Default")
      (node (ref "J12") (pin "24") (pinfunction "24_24") (pintype "bidirectional"))
    )
    (net (code "121") (name "/EXT6.LVDS_7_P") (class "Default")
      (node (ref "J12") (pin "23") (pinfunction "23_23") (pintype "bidirectional"))
    )
    (net (code "122") (name "/EXT7.LVDS_0_N") (class "Default")
      (node (ref "J13") (pin "3") (pinfunction "3_3") (pintype "bidirectional"))
    )
    (net (code "123") (name "/EXT7.LVDS_0_P") (class "Default")
      (node (ref "J13") (pin "2") (pinfunction "2_2") (pintype "bidirectional"))
    )
    (net (code "124") (name "/EXT7.LVDS_1_N") (class "Default")
      (node (ref "J13") (pin "6") (pinfunction "6_6") (pintype "bidirectional"))
    )
    (net (code "125") (name "/EXT7.LVDS_1_P") (class "Default")
      (node (ref "J13") (pin "5") (pinfunction "5_5") (pintype "bidirectional"))
    )
    (net (code "126") (name "/EXT7.LVDS_2_N") (class "Default")
      (node (ref "J13") (pin "9") (pinfunction "9_9") (pintype "bidirectional"))
    )
    (net (code "127") (name "/EXT7.LVDS_2_P") (class "Default")
      (node (ref "J13") (pin "8") (pinfunction "8_8") (pintype "bidirectional"))
    )
    (net (code "128") (name "/EXT7.LVDS_3_N") (class "Default")
      (node (ref "J13") (pin "12") (pinfunction "12_12") (pintype "bidirectional"))
    )
    (net (code "129") (name "/EXT7.LVDS_3_P") (class "Default")
      (node (ref "J13") (pin "11") (pinfunction "11_11") (pintype "bidirectional"))
    )
    (net (code "130") (name "/EXT7.LVDS_4_N") (class "Default")
      (node (ref "J13") (pin "15") (pinfunction "15_15") (pintype "bidirectional"))
    )
    (net (code "131") (name "/EXT7.LVDS_4_P") (class "Default")
      (node (ref "J13") (pin "14") (pinfunction "14_14") (pintype "bidirectional"))
    )
    (net (code "132") (name "/EXT7.LVDS_5_N") (class "Default")
      (node (ref "J13") (pin "18") (pinfunction "18_18") (pintype "bidirectional"))
    )
    (net (code "133") (name "/EXT7.LVDS_5_P") (class "Default")
      (node (ref "J13") (pin "17") (pinfunction "17_17") (pintype "bidirectional"))
    )
    (net (code "134") (name "/EXT7.LVDS_6_N") (class "Default")
      (node (ref "J13") (pin "21") (pinfunction "21_21") (pintype "bidirectional"))
    )
    (net (code "135") (name "/EXT7.LVDS_6_P") (class "Default")
      (node (ref "J13") (pin "20") (pinfunction "20_20") (pintype "bidirectional"))
    )
    (net (code "136") (name "/EXT7.LVDS_7_N") (class "Default")
      (node (ref "J13") (pin "24") (pinfunction "24_24") (pintype "bidirectional"))
    )
    (net (code "137") (name "/EXT7.LVDS_7_P") (class "Default")
      (node (ref "J13") (pin "23") (pinfunction "23_23") (pintype "bidirectional"))
    )
    (net (code "138") (name "/EXT8.LVDS_0_N") (class "Default")
      (node (ref "J14") (pin "3") (pinfunction "3_3") (pintype "bidirectional"))
    )
    (net (code "139") (name "/EXT8.LVDS_0_P") (class "Default")
      (node (ref "J14") (pin "2") (pinfunction "2_2") (pintype "bidirectional"))
    )
    (net (code "140") (name "/EXT8.LVDS_1_N") (class "Default")
      (node (ref "J14") (pin "6") (pinfunction "6_6") (pintype "bidirectional"))
    )
    (net (code "141") (name "/EXT8.LVDS_1_P") (class "Default")
      (node (ref "J14") (pin "5") (pinfunction "5_5") (pintype "bidirectional"))
    )
    (net (code "142") (name "/EXT8.LVDS_2_N") (class "Default")
      (node (ref "J14") (pin "9") (pinfunction "9_9") (pintype "bidirectional"))
    )
    (net (code "143") (name "/EXT8.LVDS_2_P") (class "Default")
      (node (ref "J14") (pin "8") (pinfunction "8_8") (pintype "bidirectional"))
    )
    (net (code "144") (name "/EXT8.LVDS_3_N") (class "Default")
      (node (ref "J14") (pin "12") (pinfunction "12_12") (pintype "bidirectional"))
    )
    (net (code "145") (name "/EXT8.LVDS_3_P") (class "Default")
      (node (ref "J14") (pin "11") (pinfunction "11_11") (pintype "bidirectional"))
    )
    (net (code "146") (name "/EXT8.LVDS_4_N") (class "Default")
      (node (ref "J14") (pin "15") (pinfunction "15_15") (pintype "bidirectional"))
    )
    (net (code "147") (name "/EXT8.LVDS_4_P") (class "Default")
      (node (ref "J14") (pin "14") (pinfunction "14_14") (pintype "bidirectional"))
    )
    (net (code "148") (name "/EXT8.LVDS_5_N") (class "Default")
      (node (ref "J14") (pin "18") (pinfunction "18_18") (pintype "bidirectional"))
    )
    (net (code "149") (name "/EXT8.LVDS_5_P") (class "Default")
      (node (ref "J14") (pin "17") (pinfunction "17_17") (pintype "bidirectional"))
    )
    (net (code "150") (name "/EXT8.LVDS_6_N") (class "Default")
      (node (ref "J14") (pin "21") (pinfunction "21_21") (pintype "bidirectional"))
    )
    (net (code "151") (name "/EXT8.LVDS_6_P") (class "Default")
      (node (ref "J14") (pin "20") (pinfunction "20_20") (pintype "bidirectional"))
    )
    (net (code "152") (name "/EXT8.LVDS_7_N") (class "Default")
      (node (ref "J14") (pin "24") (pinfunction "24_24") (pintype "bidirectional"))
    )
    (net (code "153") (name "/EXT8.LVDS_7_P") (class "Default")
      (node (ref "J14") (pin "23") (pinfunction "23_23") (pintype "bidirectional"))
    )
    (net (code "154") (name "/EXT9.LVDS_0_N") (class "Default")
      (node (ref "J15") (pin "3") (pinfunction "3_3") (pintype "bidirectional"))
    )
    (net (code "155") (name "/EXT9.LVDS_0_P") (class "Default")
      (node (ref "J15") (pin "2") (pinfunction "2_2") (pintype "bidirectional"))
    )
    (net (code "156") (name "/EXT9.LVDS_1_N") (class "Default")
      (node (ref "J15") (pin "6") (pinfunction "6_6") (pintype "bidirectional"))
    )
    (net (code "157") (name "/EXT9.LVDS_1_P") (class "Default")
      (node (ref "J15") (pin "5") (pinfunction "5_5") (pintype "bidirectional"))
    )
    (net (code "158") (name "/EXT9.LVDS_2_N") (class "Default")
      (node (ref "J15") (pin "9") (pinfunction "9_9") (pintype "bidirectional"))
    )
    (net (code "159") (name "/EXT9.LVDS_2_P") (class "Default")
      (node (ref "J15") (pin "8") (pinfunction "8_8") (pintype "bidirectional"))
    )
    (net (code "160") (name "/EXT9.LVDS_3_N") (class "Default")
      (node (ref "J15") (pin "12") (pinfunction "12_12") (pintype "bidirectional"))
    )
    (net (code "161") (name "/EXT9.LVDS_3_P") (class "Default")
      (node (ref "J15") (pin "11") (pinfunction "11_11") (pintype "bidirectional"))
    )
    (net (code "162") (name "/EXT9.LVDS_4_N") (class "Default")
      (node (ref "J15") (pin "15") (pinfunction "15_15") (pintype "bidirectional"))
    )
    (net (code "163") (name "/EXT9.LVDS_4_P") (class "Default")
      (node (ref "J15") (pin "14") (pinfunction "14_14") (pintype "bidirectional"))
    )
    (net (code "164") (name "/EXT9.LVDS_5_N") (class "Default")
      (node (ref "J15") (pin "18") (pinfunction "18_18") (pintype "bidirectional"))
    )
    (net (code "165") (name "/EXT9.LVDS_5_P") (class "Default")
      (node (ref "J15") (pin "17") (pinfunction "17_17") (pintype "bidirectional"))
    )
    (net (code "166") (name "/EXT9.LVDS_6_N") (class "Default")
      (node (ref "J15") (pin "21") (pinfunction "21_21") (pintype "bidirectional"))
    )
    (net (code "167") (name "/EXT9.LVDS_6_P") (class "Default")
      (node (ref "J15") (pin "20") (pinfunction "20_20") (pintype "bidirectional"))
    )
    (net (code "168") (name "/EXT9.LVDS_7_N") (class "Default")
      (node (ref "J15") (pin "24") (pinfunction "24_24") (pintype "bidirectional"))
    )
    (net (code "169") (name "/EXT9.LVDS_7_P") (class "Default")
      (node (ref "J15") (pin "23") (pinfunction "23_23") (pintype "bidirectional"))
    )
    (net (code "170") (name "/EXT10.LVDS_0_N") (class "Default")
      (node (ref "J16") (pin "3") (pinfunction "3_3") (pintype "bidirectional"))
    )
    (net (code "171") (name "/EXT10.LVDS_0_P") (class "Default")
      (node (ref "J16") (pin "2") (pinfunction "2_2") (pintype "bidirectional"))
    )
    (net (code "172") (name "/EXT10.LVDS_1_N") (class "Default")
      (node (ref "J16") (pin "6") (pinfunction "6_6") (pintype "bidirectional"))
    )
    (net (code "173") (name "/EXT10.LVDS_1_P") (class "Default")
      (node (ref "J16") (pin "5") (pinfunction "5_5") (pintype "bidirectional"))
    )
    (net (code "174") (name "/EXT10.LVDS_2_N") (class "Default")
      (node (ref "J16") (pin "9") (pinfunction "9_9") (pintype "bidirectional"))
    )
    (net (code "175") (name "/EXT10.LVDS_2_P") (class "Default")
      (node (ref "J16") (pin "8") (pinfunction "8_8") (pintype "bidirectional"))
    )
    (net (code "176") (name "/EXT10.LVDS_3_N") (class "Default")
      (node (ref "J16") (pin "12") (pinfunction "12_12") (pintype "bidirectional"))
    )
    (net (code "177") (name "/EXT10.LVDS_3_P") (class "Default")
      (node (ref "J16") (pin "11") (pinfunction "11_11") (pintype "bidirectional"))
    )
    (net (code "178") (name "/EXT10.LVDS_4_N") (class "Default")
      (node (ref "J16") (pin "15") (pinfunction "15_15") (pintype "bidirectional"))
    )
    (net (code "179") (name "/EXT10.LVDS_4_P") (class "Default")
      (node (ref "J16") (pin "14") (pinfunction "14_14") (pintype "bidirectional"))
    )
    (net (code "180") (name "/EXT10.LVDS_5_N") (class "Default")
      (node (ref "J16") (pin "18") (pinfunction "18_18") (pintype "bidirectional"))
    )
    (net (code "181") (name "/EXT10.LVDS_5_P") (class "Default")
      (node (ref "J16") (pin "17") (pinfunction "17_17") (pintype "bidirectional"))
    )
    (net (code "182") (name "/EXT10.LVDS_6_N") (class "Default")
      (node (ref "J16") (pin "21") (pinfunction "21_21") (pintype "bidirectional"))
    )
    (net (code "183") (name "/EXT10.LVDS_6_P") (class "Default")
      (node (ref "J16") (pin "20") (pinfunction "20_20") (pintype "bidirectional"))
    )
    (net (code "184") (name "/EXT10.LVDS_7_N") (class "Default")
      (node (ref "J16") (pin "24") (pinfunction "24_24") (pintype "bidirectional"))
    )
    (net (code "185") (name "/EXT10.LVDS_7_P") (class "Default")
      (node (ref "J16") (pin "23") (pinfunction "23_23") (pintype "bidirectional"))
    )
    (net (code "186") (name "/EXT11.LVDS_0_N") (class "Default")
      (node (ref "J17") (pin "3") (pinfunction "3_3") (pintype "bidirectional"))
    )
    (net (code "187") (name "/EXT11.LVDS_0_P") (class "Default")
      (node (ref "J17") (pin "2") (pinfunction "2_2") (pintype "bidirectional"))
    )
    (net (code "188") (name "/EXT11.LVDS_1_N") (class "Default")
      (node (ref "J17") (pin "6") (pinfunction "6_6") (pintype "bidirectional"))
    )
    (net (code "189") (name "/EXT11.LVDS_1_P") (class "Default")
      (node (ref "J17") (pin "5") (pinfunction "5_5") (pintype "bidirectional"))
    )
    (net (code "190") (name "/EXT11.LVDS_2_N") (class "Default")
      (node (ref "J17") (pin "9") (pinfunction "9_9") (pintype "bidirectional"))
    )
    (net (code "191") (name "/EXT11.LVDS_2_P") (class "Default")
      (node (ref "J17") (pin "8") (pinfunction "8_8") (pintype "bidirectional"))
    )
    (net (code "192") (name "/EXT11.LVDS_3_N") (class "Default")
      (node (ref "J17") (pin "12") (pinfunction "12_12") (pintype "bidirectional"))
    )
    (net (code "193") (name "/EXT11.LVDS_3_P") (class "Default")
      (node (ref "J17") (pin "11") (pinfunction "11_11") (pintype "bidirectional"))
    )
    (net (code "194") (name "/EXT11.LVDS_4_N") (class "Default")
      (node (ref "J17") (pin "15") (pinfunction "15_15") (pintype "bidirectional"))
    )
    (net (code "195") (name "/EXT11.LVDS_4_P") (class "Default")
      (node (ref "J17") (pin "14") (pinfunction "14_14") (pintype "bidirectional"))
    )
    (net (code "196") (name "/EXT11.LVDS_5_N") (class "Default")
      (node (ref "J17") (pin "18") (pinfunction "18_18") (pintype "bidirectional"))
    )
    (net (code "197") (name "/EXT11.LVDS_5_P") (class "Default")
      (node (ref "J17") (pin "17") (pinfunction "17_17") (pintype "bidirectional"))
    )
    (net (code "198") (name "/EXT11.LVDS_6_N") (class "Default")
      (node (ref "J17") (pin "21") (pinfunction "21_21") (pintype "bidirectional"))
    )
    (net (code "199") (name "/EXT11.LVDS_6_P") (class "Default")
      (node (ref "J17") (pin "20") (pinfunction "20_20") (pintype "bidirectional"))
    )
    (net (code "200") (name "/EXT11.LVDS_7_N") (class "Default")
      (node (ref "J17") (pin "24") (pinfunction "24_24") (pintype "bidirectional"))
    )
    (net (code "201") (name "/EXT11.LVDS_7_P") (class "Default")
      (node (ref "J17") (pin "23") (pinfunction "23_23") (pintype "bidirectional"))
    )
    (net (code "202") (name "/I2C_SCL_0") (class "Default")
      (node (ref "D3") (pin "3") (pinfunction "I/O2_3") (pintype "bidirectional"))
      (node (ref "J6") (pin "27") (pinfunction "27_27") (pintype "bidirectional"))
    )
    (net (code "203") (name "/I2C_SCL_1") (class "Default")
      (node (ref "D4") (pin "3") (pinfunction "I/O2_3") (pintype "bidirectional"))
      (node (ref "J7") (pin "27") (pinfunction "27_27") (pintype "bidirectional"))
    )
    (net (code "204") (name "/I2C_SCL_2") (class "Default")
      (node (ref "D5") (pin "3") (pinfunction "I/O2_3") (pintype "bidirectional"))
      (node (ref "J8") (pin "27") (pinfunction "27_27") (pintype "bidirectional"))
    )
    (net (code "205") (name "/I2C_SCL_3") (class "Default")
      (node (ref "D6") (pin "3") (pinfunction "I/O2_3") (pintype "bidirectional"))
      (node (ref "J9") (pin "27") (pinfunction "27_27") (pintype "bidirectional"))
    )
    (net (code "206") (name "/I2C_SCL_4") (class "Default")
      (node (ref "D7") (pin "3") (pinfunction "I/O2_3") (pintype "bidirectional"))
      (node (ref "J10") (pin "27") (pinfunction "27_27") (pintype "bidirectional"))
    )
    (net (code "207") (name "/I2C_SCL_5") (class "Default")
      (node (ref "D8") (pin "3") (pinfunction "I/O2_3") (pintype "bidirectional"))
      (node (ref "J11") (pin "27") (pinfunction "27_27") (pintype "bidirectional"))
    )
    (net (code "208") (name "/I2C_SCL_6") (class "Default")
      (node (ref "D9") (pin "3") (pinfunction "I/O2_3") (pintype "bidirectional"))
      (node (ref "J12") (pin "27") (pinfunction "27_27") (pintype "bidirectional"))
    )
    (net (code "209") (name "/I2C_SCL_7") (class "Default")
      (node (ref "D10") (pin "3") (pinfunction "I/O2_3") (pintype "bidirectional"))
      (node (ref "J13") (pin "27") (pinfunction "27_27") (pintype "bidirectional"))
    )
    (net (code "210") (name "/I2C_SCL_8") (class "Default")
      (node (ref "D11") (pin "3") (pinfunction "I/O2_3") (pintype "bidirectional"))
      (node (ref "J14") (pin "27") (pinfunction "27_27") (pintype "bidirectional"))
    )
    (net (code "211") (name "/I2C_SCL_9") (class "Default")
      (node (ref "D13") (pin "3") (pinfunction "I/O2_3") (pintype "bidirectional"))
      (node (ref "J15") (pin "27") (pinfunction "27_27") (pintype "bidirectional"))
    )
    (net (code "212") (name "/I2C_SCL_10") (class "Default")
      (node (ref "D12") (pin "3") (pinfunction "I/O2_3") (pintype "bidirectional"))
      (node (ref "J16") (pin "27") (pinfunction "27_27") (pintype "bidirectional"))
    )
    (net (code "213") (name "/I2C_SCL_11") (class "Default")
      (node (ref "D14") (pin "3") (pinfunction "I/O2_3") (pintype "bidirectional"))
      (node (ref "J17") (pin "27") (pinfunction "27_27") (pintype "bidirectional"))
    )
    (net (code "215") (name "/I2C_SDA_0") (class "Default")
      (node (ref "D3") (pin "2") (pinfunction "I/O1_2") (pintype "bidirectional"))
      (node (ref "J6") (pin "26") (pinfunction "26_26") (pintype "bidirectional"))
    )
    (net (code "216") (name "/I2C_SDA_1") (class "Default")
      (node (ref "D4") (pin "2") (pinfunction "I/O1_2") (pintype "bidirectional"))
      (node (ref "J7") (pin "26") (pinfunction "26_26") (pintype "bidirectional"))
    )
    (net (code "217") (name "/I2C_SDA_2") (class "Default")
      (node (ref "D5") (pin "2") (pinfunction "I/O1_2") (pintype "bidirectional"))
      (node (ref "J8") (pin "26") (pinfunction "26_26") (pintype "bidirectional"))
    )
    (net (code "218") (name "/I2C_SDA_3") (class "Default")
      (node (ref "D6") (pin "2") (pinfunction "I/O1_2") (pintype "bidirectional"))
      (node (ref "J9") (pin "26") (pinfunction "26_26") (pintype "bidirectional"))
    )
    (net (code "219") (name "/I2C_SDA_4") (class "Default")
      (node (ref "D7") (pin "2") (pinfunction "I/O1_2") (pintype "bidirectional"))
      (node (ref "J10") (pin "26") (pinfunction "26_26") (pintype "bidirectional"))
    )
    (net (code "220") (name "/I2C_SDA_5") (class "Default")
      (node (ref "D8") (pin "2") (pinfunction "I/O1_2") (pintype "bidirectional"))
      (node (ref "J11") (pin "26") (pinfunction "26_26") (pintype "bidirectional"))
    )
    (net (code "221") (name "/I2C_SDA_6") (class "Default")
      (node (ref "D9") (pin "2") (pinfunction "I/O1_2") (pintype "bidirectional"))
      (node (ref "J12") (pin "26") (pinfunction "26_26") (pintype "bidirectional"))
    )
    (net (code "222") (name "/I2C_SDA_7") (class "Default")
      (node (ref "D10") (pin "2") (pinfunction "I/O1_2") (pintype "bidirectional"))
      (node (ref "J13") (pin "26") (pinfunction "26_26") (pintype "bidirectional"))
    )
    (net (code "223") (name "/I2C_SDA_8") (class "Default")
      (node (ref "D11") (pin "2") (pinfunction "I/O1_2") (pintype "bidirectional"))
      (node (ref "J14") (pin "26") (pinfunction "26_26") (pintype "bidirectional"))
    )
    (net (code "224") (name "/I2C_SDA_9") (class "Default")
      (node (ref "D13") (pin "2") (pinfunction "I/O1_2") (pintype "bidirectional"))
      (node (ref "J15") (pin "26") (pinfunction "26_26") (pintype "bidirectional"))
    )
    (net (code "225") (name "/I2C_SDA_10") (class "Default")
      (node (ref "D12") (pin "2") (pinfunction "I/O1_2") (pintype "bidirectional"))
      (node (ref "J16") (pin "26") (pinfunction "26_26") (pintype "bidirectional"))
    )
    (net (code "226") (name "/I2C_SDA_11") (class "Default")
      (node (ref "D14") (pin "2") (pinfunction "I/O1_2") (pintype "bidirectional"))
      (node (ref "J17") (pin "26") (pinfunction "26_26") (pintype "bidirectional"))
    )
    (net (code "229") (name "GND") (class "Default")
      (node (ref "C30") (pin "1") (pinfunction "1_1") (pintype "passive"))
      (node (ref "C31") (pin "1") (pinfunction "1_1") (pintype "passive"))
      (node (ref "C32") (pin "1") (pinfunction "1_1") (pintype "passive"))
      (node (ref "C33") (pin "1") (pinfunction "1_1") (pintype "passive"))
      (node (ref "C34") (pin "1") (pinfunction "1_1") (pintype "passive"))
      (node (ref "C35") (pin "1") (pinfunction "1_1") (pintype "passive"))
      (node (ref "C36") (pin "1") (pinfunction "1_1") (pintype "passive"))
      (node (ref "C37") (pin "1") (pinfunction "1_1") (pintype "passive"))
      (node (ref "C39") (pin "1") (pinfunction "1_1") (pintype "passive"))
      (node (ref "C40") (pin "1") (pinfunction "1_1") (pintype "passive"))
      (node (ref "C41") (pin "1") (pinfunction "1_1") (pintype "passive"))
      (node (ref "C42") (pin "1") (pinfunction "1_1") (pintype "passive"))
      (node (ref "D10") (pin "1") (pinfunction "GND_1") (pintype "power_in"))
      (node (ref "D11") (pin "1") (pinfunction "GND_1") (pintype "power_in"))
      (node (ref "D12") (pin "1") (pinfunction "GND_1") (pintype "power_in"))
      (node (ref "D13") (pin "1") (pinfunction "GND_1") (pintype "power_in"))
      (node (ref "D14") (pin "1") (pinfunction "GND_1") (pintype "power_in"))
      (node (ref "D3") (pin "1") (pinfunction "GND_1") (pintype "power_in"))
      (node (ref "D4") (pin "1") (pinfunction "GND_1") (pintype "power_in"))
      (node (ref "D5") (pin "1") (pinfunction "GND_1") (pintype "power_in"))
      (node (ref "D6") (pin "1") (pinfunction "GND_1") (pintype "power_in"))
      (node (ref "D7") (pin "1") (pinfunction "GND_1") (pintype "power_in"))
      (node (ref "D8") (pin "1") (pinfunction "GND_1") (pintype "power_in"))
      (node (ref "D9") (pin "1") (pinfunction "GND_1") (pintype "power_in"))
      (node (ref "J10") (pin "1") (pinfunction "1_1") (pintype "bidirectional"))
      (node (ref "J10") (pin "10") (pinfunction "10_10") (pintype "bidirectional"))
      (node (ref "J10") (pin "13") (pinfunction "13_13") (pintype "bidirectional"))
      (node (ref "J10") (pin "16") (pinfunction "16_16") (pintype "bidirectional"))
      (node (ref "J10") (pin "19") (pinfunction "19_19") (pintype "bidirectional"))
      (node (ref "J10") (pin "22") (pinfunction "22_22") (pintype "bidirectional"))
      (node (ref "J10") (pin "25") (pinfunction "25_25") (pintype "bidirectional"))
      (node (ref "J10") (pin "4") (pinfunction "4_4") (pintype "bidirectional"))
      (node (ref "J10") (pin "7") (pinfunction "7_7") (pintype "bidirectional"))
      (node (ref "J11") (pin "1") (pinfunction "1_1") (pintype "bidirectional"))
      (node (ref "J11") (pin "10") (pinfunction "10_10") (pintype "bidirectional"))
      (node (ref "J11") (pin "13") (pinfunction "13_13") (pintype "bidirectional"))
      (node (ref "J11") (pin "16") (pinfunction "16_16") (pintype "bidirectional"))
      (node (ref "J11") (pin "19") (pinfunction "19_19") (pintype "bidirectional"))
      (node (ref "J11") (pin "22") (pinfunction "22_22") (pintype "bidirectional"))
      (node (ref "J11") (pin "25") (pinfunction "25_25") (pintype "bidirectional"))
      (node (ref "J11") (pin "4") (pinfunction "4_4") (pintype "bidirectional"))
      (node (ref "J11") (pin "7") (pinfunction "7_7") (pintype "bidirectional"))
      (node (ref "J12") (pin "1") (pinfunction "1_1") (pintype "bidirectional"))
      (node (ref "J12") (pin "10") (pinfunction "10_10") (pintype "bidirectional"))
      (node (ref "J12") (pin "13") (pinfunction "13_13") (pintype "bidirectional"))
      (node (ref "J12") (pin "16") (pinfunction "16_16") (pintype "bidirectional"))
      (node (ref "J12") (pin "19") (pinfunction "19_19") (pintype "bidirectional"))
      (node (ref "J12") (pin "22") (pinfunction "22_22") (pintype "bidirectional"))
      (node (ref "J12") (pin "25") (pinfunction "25_25") (pintype "bidirectional"))
      (node (ref "J12") (pin "4") (pinfunction "4_4") (pintype "bidirectional"))
      (node (ref "J12") (pin "7") (pinfunction "7_7") (pintype "bidirectional"))
      (node (ref "J13") (pin "1") (pinfunction "1_1") (pintype "bidirectional"))
      (node (ref "J13") (pin "10") (pinfunction "10_10") (pintype "bidirectional"))
      (node (ref "J13") (pin "13") (pinfunction "13_13") (pintype "bidirectional"))
      (node (ref "J13") (pin "16") (pinfunction "16_16") (pintype "bidirectional"))
      (node (ref "J13") (pin "19") (pinfunction "19_19") (pintype "bidirectional"))
      (node (ref "J13") (pin "22") (pinfunction "22_22") (pintype "bidirectional"))
      (node (ref "J13") (pin "25") (pinfunction "25_25") (pintype "bidirectional"))
      (node (ref "J13") (pin "4") (pinfunction "4_4") (pintype "bidirectional"))
      (node (ref "J13") (pin "7") (pinfunction "7_7") (pintype "bidirectional"))
      (node (ref "J14") (pin "1") (pinfunction "1_1") (pintype "bidirectional"))
      (node (ref "J14") (pin "10") (pinfunction "10_10") (pintype "bidirectional"))
      (node (ref "J14") (pin "13") (pinfunction "13_13") (pintype "bidirectional"))
      (node (ref "J14") (pin "16") (pinfunction "16_16") (pintype "bidirectional"))
      (node (ref "J14") (pin "19") (pinfunction "19_19") (pintype "bidirectional"))
      (node (ref "J14") (pin "22") (pinfunction "22_22") (pintype "bidirectional"))
      (node (ref "J14") (pin "25") (pinfunction "25_25") (pintype "bidirectional"))
      (node (ref "J14") (pin "4") (pinfunction "4_4") (pintype "bidirectional"))
      (node (ref "J14") (pin "7") (pinfunction "7_7") (pintype "bidirectional"))
      (node (ref "J15") (pin "1") (pinfunction "1_1") (pintype "bidirectional"))
      (node (ref "J15") (pin "10") (pinfunction "10_10") (pintype "bidirectional"))
      (node (ref "J15") (pin "13") (pinfunction "13_13") (pintype "bidirectional"))
      (node (ref "J15") (pin "16") (pinfunction "16_16") (pintype "bidirectional"))
      (node (ref "J15") (pin "19") (pinfunction "19_19") (pintype "bidirectional"))
      (node (ref "J15") (pin "22") (pinfunction "22_22") (pintype "bidirectional"))
      (node (ref "J15") (pin "25") (pinfunction "25_25") (pintype "bidirectional"))
      (node (ref "J15") (pin "4") (pinfunction "4_4") (pintype "bidirectional"))
      (node (ref "J15") (pin "7") (pinfunction "7_7") (pintype "bidirectional"))
      (node (ref "J16") (pin "1") (pinfunction "1_1") (pintype "bidirectional"))
      (node (ref "J16") (pin "10") (pinfunction "10_10") (pintype "bidirectional"))
      (node (ref "J16") (pin "13") (pinfunction "13_13") (pintype "bidirectional"))
      (node (ref "J16") (pin "16") (pinfunction "16_16") (pintype "bidirectional"))
      (node (ref "J16") (pin "19") (pinfunction "19_19") (pintype "bidirectional"))
      (node (ref "J16") (pin "22") (pinfunction "22_22") (pintype "bidirectional"))
      (node (ref "J16") (pin "25") (pinfunction "25_25") (pintype "bidirectional"))
      (node (ref "J16") (pin "4") (pinfunction "4_4") (pintype "bidirectional"))
      (node (ref "J16") (pin "7") (pinfunction "7_7") (pintype "bidirectional"))
      (node (ref "J17") (pin "1") (pinfunction "1_1") (pintype "bidirectional"))
      (node (ref "J17") (pin "10") (pinfunction "10_10") (pintype "bidirectional"))
      (node (ref "J17") (pin "13") (pinfunction "13_13") (pintype "bidirectional"))
      (node (ref "J17") (pin "16") (pinfunction "16_16") (pintype "bidirectional"))
      (node (ref "J17") (pin "19") (pinfunction "19_19") (pintype "bidirectional"))
      (node (ref "J17") (pin "22") (pinfunction "22_22") (pintype "bidirectional"))
      (node (ref "J17") (pin "25") (pinfunction "25_25") (pintype "bidirectional"))
      (node (ref "J17") (pin "4") (pinfunction "4_4") (pintype "bidirectional"))
      (node (ref "J17") (pin "7") (pinfunction "7_7") (pintype "bidirectional"))
      (node (ref "J6") (pin "1") (pinfunction "1_1") (pintype "bidirectional"))
      (node (ref "J6") (pin "10") (pinfunction "10_10") (pintype "bidirectional"))
      (node (ref "J6") (pin "13") (pinfunction "13_13") (pintype "bidirectional"))
      (node (ref "J6") (pin "16") (pinfunction "16_16") (pintype "bidirectional"))
      (node (ref "J6") (pin "19") (pinfunction "19_19") (pintype "bidirectional"))
      (node (ref "J6") (pin "22") (pinfunction "22_22") (pintype "bidirectional"))
      (node (ref "J6") (pin "25") (pinfunction "25_25") (pintype "bidirectional"))
      (node (ref "J6") (pin "4") (pinfunction "4_4") (pintype "bidirectional"))
      (node (ref "J6") (pin "7") (pinfunction "7_7") (pintype "bidirectional"))
      (node (ref "J7") (pin "1") (pinfunction "1_1") (pintype "bidirectional"))
      (node (ref "J7") (pin "10") (pinfunction "10_10") (pintype "bidirectional"))
      (node (ref "J7") (pin "13") (pinfunction "13_13") (pintype "bidirectional"))
      (node (ref "J7") (pin "16") (pinfunction "16_16") (pintype "bidirectional"))
      (node (ref "J7") (pin "19") (pinfunction "19_19") (pintype "bidirectional"))
      (node (ref "J7") (pin "22") (pinfunction "22_22") (pintype "bidirectional"))
      (node (ref "J7") (pin "25") (pinfunction "25_25") (pintype "bidirectional"))
      (node (ref "J7") (pin "4") (pinfunction "4_4") (pintype "bidirectional"))
      (node (ref "J7") (pin "7") (pinfunction "7_7") (pintype "bidirectional"))
      (node (ref "J8") (pin "1") (pinfunction "1_1") (pintype "bidirectional"))
      (node (ref "J8") (pin "10") (pinfunction "10_10") (pintype "bidirectional"))
      (node (ref "J8") (pin "13") (pinfunction "13_13") (pintype "bidirectional"))
      (node (ref "J8") (pin "16") (pinfunction "16_16") (pintype "bidirectional"))
      (node (ref "J8") (pin "19") (pinfunction "19_19") (pintype "bidirectional"))
      (node (ref "J8") (pin "22") (pinfunction "22_22") (pintype "bidirectional"))
      (node (ref "J8") (pin "25") (pinfunction "25_25") (pintype "bidirectional"))
      (node (ref "J8") (pin "4") (pinfunction "4_4") (pintype "bidirectional"))
      (node (ref "J8") (pin "7") (pinfunction "7_7") (pintype "bidirectional"))
      (node (ref "J9") (pin "1") (pinfunction "1_1") (pintype "bidirectional"))
      (node (ref "J9") (pin "10") (pinfunction "10_10") (pintype "bidirectional"))
      (node (ref "J9") (pin "13") (pinfunction "13_13") (pintype "bidirectional"))
      (node (ref "J9") (pin "16") (pinfunction "16_16") (pintype "bidirectional"))
      (node (ref "J9") (pin "19") (pinfunction "19_19") (pintype "bidirectional"))
      (node (ref "J9") (pin "22") (pinfunction "22_22") (pintype "bidirectional"))
      (node (ref "J9") (pin "25") (pinfunction "25_25") (pintype "bidirectional"))
      (node (ref "J9") (pin "4") (pinfunction "4_4") (pintype "bidirectional"))
      (node (ref "J9") (pin "7") (pinfunction "7_7") (pintype "bidirectional"))
    )
    (net (code "230") (name "P3V3") (class "Default")
      (node (ref "C30") (pin "2") (pinfunction "2_2") (pintype "passive"))
      (node (ref "C31") (pin "2") (pinfunction "2_2") (pintype "passive"))
      (node (ref "C32") (pin "2") (pinfunction "2_2") (pintype "passive"))
      (node (ref "C33") (pin "2") (pinfunction "2_2") (pintype "passive"))
      (node (ref "C34") (pin "2") (pinfunction "2_2") (pintype "passive"))
      (node (ref "C35") (pin "2") (pinfunction "2_2") (pintype "passive"))
      (node (ref "C36") (pin "2") (pinfunction "2_2") (pintype "passive"))
      (node (ref "C37") (pin "2") (pinfunction "2_2") (pintype "passive"))
      (node (ref "C39") (pin "2") (pinfunction "2_2") (pintype "passive"))
      (node (ref "C40") (pin "2") (pinfunction "2_2") (pintype "passive"))
      (node (ref "C41") (pin "2") (pinfunction "2_2") (pintype "passive"))
      (node (ref "C42") (pin "2") (pinfunction "2_2") (pintype "passive"))
      (node (ref "D10") (pin "4") (pinfunction "VCC_4") (pintype "power_in"))
      (node (ref "D11") (pin "4") (pinfunction "VCC_4") (pintype "power_in"))
      (node (ref "D12") (pin "4") (pinfunction "VCC_4") (pintype "power_in"))
      (node (ref "D13") (pin "4") (pinfunction "VCC_4") (pintype "power_in"))
      (node (ref "D14") (pin "4") (pinfunction "VCC_4") (pintype "power_in"))
      (node (ref "D3") (pin "4") (pinfunction "VCC_4") (pintype "power_in"))
      (node (ref "D4") (pin "4") (pinfunction "VCC_4") (pintype "power_in"))
      (node (ref "D5") (pin "4") (pinfunction "VCC_4") (pintype "power_in"))
      (node (ref "D6") (pin "4") (pinfunction "VCC_4") (pintype "power_in"))
      (node (ref "D7") (pin "4") (pinfunction "VCC_4") (pintype "power_in"))
      (node (ref "D8") (pin "4") (pinfunction "VCC_4") (pintype "power_in"))
      (node (ref "D9") (pin "4") (pinfunction "VCC_4") (pintype "power_in"))
      (node (ref "J10") (pin "30") (pinfunction "30_30") (pintype "bidirectional"))
      (node (ref "J11") (pin "30") (pinfunction "30_30") (pintype "bidirectional"))
      (node (ref "J12") (pin "30") (pinfunction "30_30") (pintype "bidirectional"))
      (node (ref "J13") (pin "30") (pinfunction "30_30") (pintype "bidirectional"))
      (node (ref "J14") (pin "30") (pinfunction "30_30") (pintype "bidirectional"))
      (node (ref "J15") (pin "30") (pinfunction "30_30") (pintype "bidirectional"))
      (node (ref "J16") (pin "30") (pinfunction "30_30") (pintype "bidirectional"))
      (node (ref "J17") (pin "30") (pinfunction "30_30") (pintype "bidirectional"))
      (node (ref "J6") (pin "30") (pinfunction "30_30") (pintype "bidirectional"))
      (node (ref "J7") (pin "30") (pinfunction "30_30") (pintype "bidirectional"))
      (node (ref "J8") (pin "30") (pinfunction "30_30") (pintype "bidirectional"))
      (node (ref "J9") (pin "30") (pinfunction "30_30") (pintype "bidirectional"))
    )
    (net (code "231") (name "P12V0") (class "Default")
      (node (ref "J10") (pin "28") (pinfunction "28_28") (pintype "bidirectional"))
      (node (ref "J10") (pin "29") (pinfunction "29_29") (pintype "bidirectional"))
      (node (ref "J11") (pin "28") (pinfunction "28_28") (pintype "bidirectional"))
      (node (ref "J11") (pin "29") (pinfunction "29_29") (pintype "bidirectional"))
      (node (ref "J12") (pin "28") (pinfunction "28_28") (pintype "bidirectional"))
      (node (ref "J12") (pin "29") (pinfunction "29_29") (pintype "bidirectional"))
      (node (ref "J13") (pin "28") (pinfunction "28_28") (pintype "bidirectional"))
      (node (ref "J13") (pin "29") (pinfunction "29_29") (pintype "bidirectional"))
      (node (ref "J14") (pin "28") (pinfunction "28_28") (pintype "bidirectional"))
      (node (ref "J14") (pin "29") (pinfunction "29_29") (pintype "bidirectional"))
      (node (ref "J15") (pin "28") (pinfunction "28_28") (pintype "bidirectional"))
      (node (ref "J15") (pin "29") (pinfunction "29_29") (pintype "bidirectional"))
      (node (ref "J16") (pin "28") (pinfunction "28_28") (pintype "bidirectional"))
      (node (ref "J16") (pin "29") (pinfunction "29_29") (pintype "bidirectional"))
      (node (ref "J17") (pin "28") (pinfunction "28_28") (pintype "bidirectional"))
      (node (ref "J17") (pin "29") (pinfunction "29_29") (pintype "bidirectional"))
      (node (ref "J6") (pin "28") (pinfunction "28_28") (pintype "bidirectional"))
      (node (ref "J6") (pin "29") (pinfunction "29_29") (pintype "bidirectional"))
      (node (ref "J7") (pin "28") (pinfunction "28_28") (pintype "bidirectional"))
      (node (ref "J7") (pin "29") (pinfunction "29_29") (pintype "bidirectional"))
      (node (ref "J8") (pin "28") (pinfunction "28_28") (pintype "bidirectional"))
      (node (ref "J8") (pin "29") (pinfunction "29_29") (pintype "bidirectional"))
      (node (ref "J9") (pin "28") (pinfunction "28_28") (pintype "bidirectional"))
      (node (ref "J9") (pin "29") (pinfunction "29_29") (pintype "bidirectional"))
    )
  )
)
